# Kasli-SOC_power.net
KiCad netlist of a schematic drawn in Altium Designer
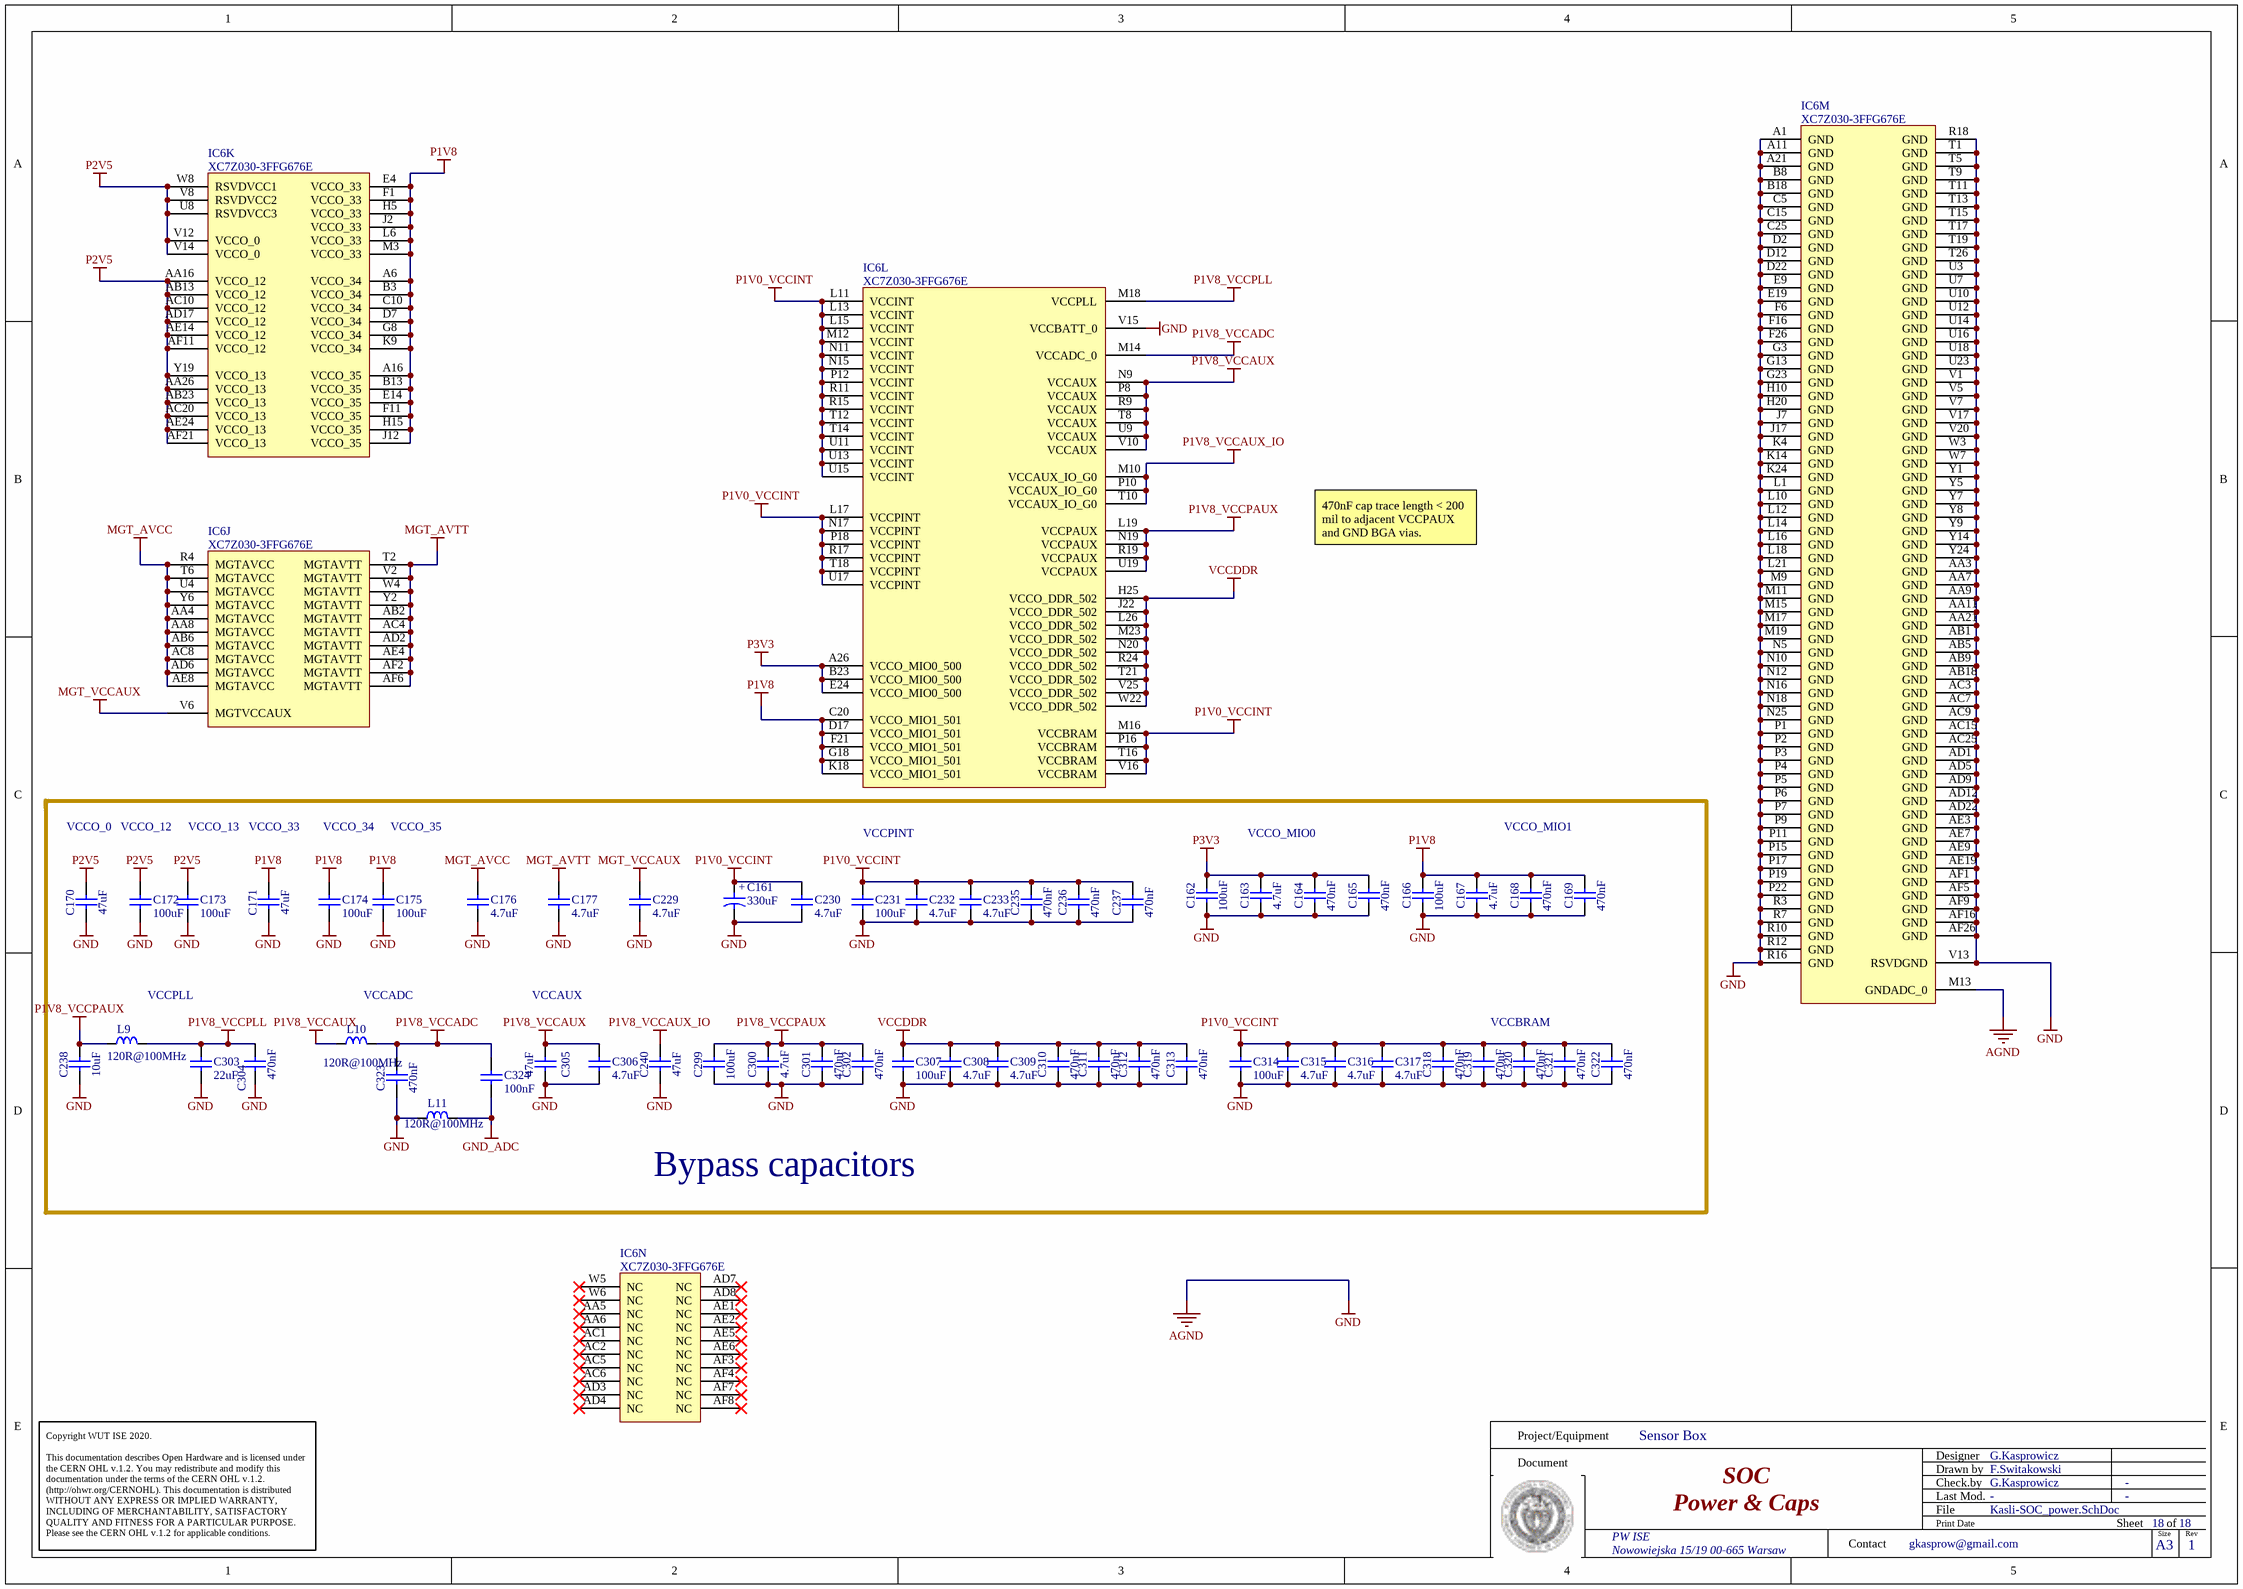
[diagram p0: Kasli-SOC_power.SchDoc]

(export (version "E")
  (design (tool "Eeschema 10.0.6"))
  (components
    (comp (ref "C161")
      (value "330uF")
      (footprint "CAPMP7343X310N")
      (description "Polarised capacitor")
      (fields
        (field (name "PART NUMBER") "CTE7343-31_330UF_6.3V_20%_LESR0015_KEMET_T520")
        (field (name "VOLTAGE") "6.3V")
        (field (name "AUTHOR") "CERN DEM JLC")
      )
      (libsource (lib "Capacitors") (part "Capacitor - polarized"))
    )
    (comp (ref "C162")
      (value "100uF")
      (footprint "CAPC3216X180N")
      (description "Non-polarised capacitor")
      (fields
        (field (name "PART NUMBER") "CC1206_100UF_6.3V_20%_X5R")
        (field (name "VOLTAGE") "6.3V")
        (field (name "AUTHOR") "CERN DEM JLC")
      )
      (libsource (lib "Capacitors") (part "Capacitor - non polarized"))
    )
    (comp (ref "C163")
      (value "4.7uF")
      (footprint "CAPC1005X55N")
      (description "Non-polarised capacitor")
      (fields
        (field (name "PART NUMBER") "CC0402_4.7UF_6.3V_20%_X5R")
        (field (name "VOLTAGE") "6.3V")
        (field (name "AUTHOR") "CERN DEM JLC")
      )
      (libsource (lib "Capacitors") (part "Capacitor - non polarized"))
    )
    (comp (ref "C164")
      (value "470nF")
      (footprint "CAPC1005X55N")
      (description "Non-polarised capacitor")
      (fields
        (field (name "PART NUMBER") "CC0402_470NF_16V_10%_X5R")
        (field (name "VOLTAGE") "16V")
        (field (name "AUTHOR") "CERN DEM JLC")
      )
      (libsource (lib "Capacitors") (part "Capacitor - non polarized"))
    )
    (comp (ref "C165")
      (value "470nF")
      (footprint "CAPC1005X55N")
      (description "Non-polarised capacitor")
      (fields
        (field (name "PART NUMBER") "CC0402_470NF_16V_10%_X5R")
        (field (name "VOLTAGE") "16V")
        (field (name "AUTHOR") "CERN DEM JLC")
      )
      (libsource (lib "Capacitors") (part "Capacitor - non polarized"))
    )
    (comp (ref "C166")
      (value "100uF")
      (footprint "CAPC3216X180N")
      (description "Non-polarised capacitor")
      (fields
        (field (name "PART NUMBER") "CC1206_100UF_6.3V_20%_X5R")
        (field (name "VOLTAGE") "6.3V")
        (field (name "AUTHOR") "CERN DEM JLC")
      )
      (libsource (lib "Capacitors") (part "Capacitor - non polarized"))
    )
    (comp (ref "C167")
      (value "4.7uF")
      (footprint "CAPC1005X55N")
      (description "Non-polarised capacitor")
      (fields
        (field (name "PART NUMBER") "CC0402_4.7UF_6.3V_20%_X5R")
        (field (name "VOLTAGE") "6.3V")
        (field (name "AUTHOR") "CERN DEM JLC")
      )
      (libsource (lib "Capacitors") (part "Capacitor - non polarized"))
    )
    (comp (ref "C168")
      (value "470nF")
      (footprint "CAPC1005X55N")
      (description "Non-polarised capacitor")
      (fields
        (field (name "PART NUMBER") "CC0402_470NF_16V_10%_X5R")
        (field (name "VOLTAGE") "16V")
        (field (name "AUTHOR") "CERN DEM JLC")
      )
      (libsource (lib "Capacitors") (part "Capacitor - non polarized"))
    )
    (comp (ref "C169")
      (value "470nF")
      (footprint "CAPC1005X55N")
      (description "Non-polarised capacitor")
      (fields
        (field (name "PART NUMBER") "CC0402_470NF_16V_10%_X5R")
        (field (name "VOLTAGE") "16V")
        (field (name "AUTHOR") "CERN DEM JLC")
      )
      (libsource (lib "Capacitors") (part "Capacitor - non polarized"))
    )
    (comp (ref "C170")
      (value "47uF")
      (footprint "CAPC3216X180N")
      (description "Non-polarised capacitor")
      (fields
        (field (name "PART NUMBER") "CC1206_47UF_10V_10%_X5R")
        (field (name "VOLTAGE") "10V")
        (field (name "AUTHOR") "CERN DEM MR")
      )
      (libsource (lib "Capacitors") (part "Capacitor - non polarized"))
    )
    (comp (ref "C171")
      (value "47uF")
      (footprint "CAPC3216X180N")
      (description "Non-polarised capacitor")
      (fields
        (field (name "PART NUMBER") "CC1206_47UF_10V_10%_X5R")
        (field (name "VOLTAGE") "10V")
        (field (name "AUTHOR") "CERN DEM MR")
      )
      (libsource (lib "Capacitors") (part "Capacitor - non polarized"))
    )
    (comp (ref "C172")
      (value "100uF")
      (footprint "CAPC3216X180N")
      (description "Non-polarised capacitor")
      (fields
        (field (name "PART NUMBER") "CC1206_100UF_6.3V_20%_X5R")
        (field (name "VOLTAGE") "6.3V")
        (field (name "AUTHOR") "CERN DEM JLC")
      )
      (libsource (lib "Capacitors") (part "Capacitor - non polarized"))
    )
    (comp (ref "C173")
      (value "100uF")
      (footprint "CAPC3216X180N")
      (description "Non-polarised capacitor")
      (fields
        (field (name "PART NUMBER") "CC1206_100UF_6.3V_20%_X5R")
        (field (name "VOLTAGE") "6.3V")
        (field (name "AUTHOR") "CERN DEM JLC")
      )
      (libsource (lib "Capacitors") (part "Capacitor - non polarized"))
    )
    (comp (ref "C174")
      (value "100uF")
      (footprint "CAPC3216X180N")
      (description "Non-polarised capacitor")
      (fields
        (field (name "PART NUMBER") "CC1206_100UF_6.3V_20%_X5R")
        (field (name "VOLTAGE") "6.3V")
        (field (name "AUTHOR") "CERN DEM JLC")
      )
      (libsource (lib "Capacitors") (part "Capacitor - non polarized"))
    )
    (comp (ref "C175")
      (value "100uF")
      (footprint "CAPC3216X180N")
      (description "Non-polarised capacitor")
      (fields
        (field (name "PART NUMBER") "CC1206_100UF_6.3V_20%_X5R")
        (field (name "VOLTAGE") "6.3V")
        (field (name "AUTHOR") "CERN DEM JLC")
      )
      (libsource (lib "Capacitors") (part "Capacitor - non polarized"))
    )
    (comp (ref "C176")
      (value "4.7uF")
      (footprint "CAPC1608X87N")
      (description "Non-polarised capacitor")
      (fields
        (field (name "PART NUMBER") "CC0603_4.7UF_6.3V_10%_X5R")
        (field (name "VOLTAGE") "6.3V")
        (field (name "AUTHOR") "CERN DEM JLC")
      )
      (libsource (lib "Capacitors") (part "Capacitor - non polarized"))
    )
    (comp (ref "C177")
      (value "4.7uF")
      (footprint "CAPC1608X87N")
      (description "Non-polarised capacitor")
      (fields
        (field (name "PART NUMBER") "CC0603_4.7UF_6.3V_10%_X5R")
        (field (name "VOLTAGE") "6.3V")
        (field (name "AUTHOR") "CERN DEM JLC")
      )
      (libsource (lib "Capacitors") (part "Capacitor - non polarized"))
    )
    (comp (ref "C229")
      (value "4.7uF")
      (footprint "CAPC1608X87N")
      (description "Non-polarised capacitor")
      (fields
        (field (name "PART NUMBER") "CC0603_4.7UF_6.3V_10%_X5R")
        (field (name "VOLTAGE") "6.3V")
        (field (name "AUTHOR") "CERN DEM JLC")
      )
      (libsource (lib "Capacitors") (part "Capacitor - non polarized"))
    )
    (comp (ref "C230")
      (value "4.7uF")
      (footprint "CAPC1608X87N")
      (description "Non-polarised capacitor")
      (fields
        (field (name "PART NUMBER") "CC0603_4.7UF_6.3V_10%_X5R")
        (field (name "VOLTAGE") "6.3V")
        (field (name "AUTHOR") "CERN DEM JLC")
      )
      (libsource (lib "Capacitors") (part "Capacitor - non polarized"))
    )
    (comp (ref "C231")
      (value "100uF")
      (footprint "CAPC3216X180N")
      (description "Non-polarised capacitor")
      (fields
        (field (name "PART NUMBER") "CC1206_100UF_6.3V_20%_X5R")
        (field (name "VOLTAGE") "6.3V")
        (field (name "AUTHOR") "CERN DEM JLC")
      )
      (libsource (lib "Capacitors") (part "Capacitor - non polarized"))
    )
    (comp (ref "C232")
      (value "4.7uF")
      (footprint "CAPC1608X87N")
      (description "Non-polarised capacitor")
      (fields
        (field (name "PART NUMBER") "CC0603_4.7UF_6.3V_10%_X5R")
        (field (name "VOLTAGE") "6.3V")
        (field (name "AUTHOR") "CERN DEM JLC")
      )
      (libsource (lib "Capacitors") (part "Capacitor - non polarized"))
    )
    (comp (ref "C233")
      (value "4.7uF")
      (footprint "CAPC1608X87N")
      (description "Non-polarised capacitor")
      (fields
        (field (name "PART NUMBER") "CC0603_4.7UF_6.3V_10%_X5R")
        (field (name "VOLTAGE") "6.3V")
        (field (name "AUTHOR") "CERN DEM JLC")
      )
      (libsource (lib "Capacitors") (part "Capacitor - non polarized"))
    )
    (comp (ref "C235")
      (value "470nF")
      (footprint "CAPC1005X55N")
      (description "Non-polarised capacitor")
      (fields
        (field (name "PART NUMBER") "CC0402_470NF_16V_10%_X5R")
        (field (name "VOLTAGE") "16V")
        (field (name "AUTHOR") "CERN DEM JLC")
      )
      (libsource (lib "Capacitors") (part "Capacitor - non polarized"))
    )
    (comp (ref "C236")
      (value "470nF")
      (footprint "CAPC1005X55N")
      (description "Non-polarised capacitor")
      (fields
        (field (name "PART NUMBER") "CC0402_470NF_16V_10%_X5R")
        (field (name "VOLTAGE") "16V")
        (field (name "AUTHOR") "CERN DEM JLC")
      )
      (libsource (lib "Capacitors") (part "Capacitor - non polarized"))
    )
    (comp (ref "C237")
      (value "470nF")
      (footprint "CAPC1005X55N")
      (description "Non-polarised capacitor")
      (fields
        (field (name "PART NUMBER") "CC0402_470NF_16V_10%_X5R")
        (field (name "VOLTAGE") "16V")
        (field (name "AUTHOR") "CERN DEM JLC")
      )
      (libsource (lib "Capacitors") (part "Capacitor - non polarized"))
    )
    (comp (ref "C238")
      (value "10uF")
      (footprint "CAPC1005X70N")
      (description "Non-polarised capacitor")
      (fields
        (field (name "PART NUMBER") "CC0402_10UF_6.3V_20%_X5R")
        (field (name "VOLTAGE") "6.3V")
        (field (name "AUTHOR") "CERN DEM JLC")
      )
      (libsource (lib "Capacitors") (part "Capacitor - non polarized"))
    )
    (comp (ref "C240")
      (value "47uF")
      (footprint "CAPC3216X180N")
      (description "Non-polarised capacitor")
      (fields
        (field (name "PART NUMBER") "CC1206_47UF_10V_10%_X5R")
        (field (name "VOLTAGE") "10V")
        (field (name "AUTHOR") "CERN DEM MR")
      )
      (libsource (lib "Capacitors") (part "Capacitor - non polarized"))
    )
    (comp (ref "C299")
      (value "100uF")
      (footprint "CAPC3216X180N")
      (description "Non-polarised capacitor")
      (fields
        (field (name "PART NUMBER") "CC1206_100UF_6.3V_20%_X5R")
        (field (name "VOLTAGE") "6.3V")
        (field (name "AUTHOR") "CERN DEM JLC")
      )
      (libsource (lib "Capacitors") (part "Capacitor - non polarized"))
    )
    (comp (ref "C300")
      (value "4.7uF")
      (footprint "CAPC1005X55N")
      (description "Non-polarised capacitor")
      (fields
        (field (name "PART NUMBER") "CC0402_4.7UF_6.3V_20%_X5R")
        (field (name "VOLTAGE") "6.3V")
        (field (name "AUTHOR") "CERN DEM JLC")
      )
      (libsource (lib "Capacitors") (part "Capacitor - non polarized"))
    )
    (comp (ref "C301")
      (value "470nF")
      (footprint "CAPC1005X55N")
      (description "Non-polarised capacitor")
      (fields
        (field (name "PART NUMBER") "CC0402_470NF_16V_10%_X5R")
        (field (name "VOLTAGE") "16V")
        (field (name "AUTHOR") "CERN DEM JLC")
      )
      (libsource (lib "Capacitors") (part "Capacitor - non polarized"))
    )
    (comp (ref "C302")
      (value "470nF")
      (footprint "CAPC1005X55N")
      (description "Non-polarised capacitor")
      (fields
        (field (name "PART NUMBER") "CC0402_470NF_16V_10%_X5R")
        (field (name "VOLTAGE") "16V")
        (field (name "AUTHOR") "CERN DEM JLC")
      )
      (libsource (lib "Capacitors") (part "Capacitor - non polarized"))
    )
    (comp (ref "C303")
      (value "22uF")
      (footprint "CAPC3216X180N")
      (description "Non-polarised capacitor")
      (fields
        (field (name "PART NUMBER") "CC1206_22UF_10V_10%_X7R")
        (field (name "VOLTAGE") "10V")
        (field (name "AUTHOR") "CERN DEM JLC")
      )
      (libsource (lib "Capacitors") (part "Capacitor - non polarized"))
    )
    (comp (ref "C304")
      (value "470nF")
      (footprint "CAPC1005X55N")
      (description "Non-polarised capacitor")
      (fields
        (field (name "PART NUMBER") "CC0402_470NF_16V_10%_X5R")
        (field (name "VOLTAGE") "16V")
        (field (name "AUTHOR") "CERN DEM JLC")
      )
      (libsource (lib "Capacitors") (part "Capacitor - non polarized"))
    )
    (comp (ref "C305")
      (value "47uF")
      (footprint "CAPC3216X180N")
      (description "Non-polarised capacitor")
      (fields
        (field (name "PART NUMBER") "CC1206_47UF_10V_10%_X5R")
        (field (name "VOLTAGE") "10V")
        (field (name "AUTHOR") "CERN DEM MR")
      )
      (libsource (lib "Capacitors") (part "Capacitor - non polarized"))
    )
    (comp (ref "C306")
      (value "4.7uF")
      (footprint "CAPC1608X87N")
      (description "Non-polarised capacitor")
      (fields
        (field (name "PART NUMBER") "CC0603_4.7UF_6.3V_10%_X5R")
        (field (name "VOLTAGE") "6.3V")
        (field (name "AUTHOR") "CERN DEM JLC")
      )
      (libsource (lib "Capacitors") (part "Capacitor - non polarized"))
    )
    (comp (ref "C307")
      (value "100uF")
      (footprint "CAPC3216X180N")
      (description "Non-polarised capacitor")
      (fields
        (field (name "PART NUMBER") "CC1206_100UF_6.3V_20%_X5R")
        (field (name "VOLTAGE") "6.3V")
        (field (name "AUTHOR") "CERN DEM JLC")
      )
      (libsource (lib "Capacitors") (part "Capacitor - non polarized"))
    )
    (comp (ref "C308")
      (value "4.7uF")
      (footprint "CAPC1608X87N")
      (description "Non-polarised capacitor")
      (fields
        (field (name "PART NUMBER") "CC0603_4.7UF_6.3V_10%_X5R")
        (field (name "VOLTAGE") "6.3V")
        (field (name "AUTHOR") "CERN DEM JLC")
      )
      (libsource (lib "Capacitors") (part "Capacitor - non polarized"))
    )
    (comp (ref "C309")
      (value "4.7uF")
      (footprint "CAPC1608X87N")
      (description "Non-polarised capacitor")
      (fields
        (field (name "PART NUMBER") "CC0603_4.7UF_6.3V_10%_X5R")
        (field (name "VOLTAGE") "6.3V")
        (field (name "AUTHOR") "CERN DEM JLC")
      )
      (libsource (lib "Capacitors") (part "Capacitor - non polarized"))
    )
    (comp (ref "C310")
      (value "470nF")
      (footprint "CAPC1005X55N")
      (description "Non-polarised capacitor")
      (fields
        (field (name "PART NUMBER") "CC0402_470NF_16V_10%_X5R")
        (field (name "VOLTAGE") "16V")
        (field (name "AUTHOR") "CERN DEM JLC")
      )
      (libsource (lib "Capacitors") (part "Capacitor - non polarized"))
    )
    (comp (ref "C311")
      (value "470nF")
      (footprint "CAPC1005X55N")
      (description "Non-polarised capacitor")
      (fields
        (field (name "PART NUMBER") "CC0402_470NF_16V_10%_X5R")
        (field (name "VOLTAGE") "16V")
        (field (name "AUTHOR") "CERN DEM JLC")
      )
      (libsource (lib "Capacitors") (part "Capacitor - non polarized"))
    )
    (comp (ref "C312")
      (value "470nF")
      (footprint "CAPC1005X55N")
      (description "Non-polarised capacitor")
      (fields
        (field (name "PART NUMBER") "CC0402_470NF_16V_10%_X5R")
        (field (name "VOLTAGE") "16V")
        (field (name "AUTHOR") "CERN DEM JLC")
      )
      (libsource (lib "Capacitors") (part "Capacitor - non polarized"))
    )
    (comp (ref "C313")
      (value "470nF")
      (footprint "CAPC1005X55N")
      (description "Non-polarised capacitor")
      (fields
        (field (name "PART NUMBER") "CC0402_470NF_16V_10%_X5R")
        (field (name "VOLTAGE") "16V")
        (field (name "AUTHOR") "CERN DEM JLC")
      )
      (libsource (lib "Capacitors") (part "Capacitor - non polarized"))
    )
    (comp (ref "C314")
      (value "100uF")
      (footprint "CAPC3216X180N")
      (description "Non-polarised capacitor")
      (fields
        (field (name "PART NUMBER") "CC1206_100UF_6.3V_20%_X5R")
        (field (name "VOLTAGE") "6.3V")
        (field (name "AUTHOR") "CERN DEM JLC")
      )
      (libsource (lib "Capacitors") (part "Capacitor - non polarized"))
    )
    (comp (ref "C315")
      (value "4.7uF")
      (footprint "CAPC1608X87N")
      (description "Non-polarised capacitor")
      (fields
        (field (name "PART NUMBER") "CC0603_4.7UF_6.3V_10%_X5R")
        (field (name "VOLTAGE") "6.3V")
        (field (name "AUTHOR") "CERN DEM JLC")
      )
      (libsource (lib "Capacitors") (part "Capacitor - non polarized"))
    )
    (comp (ref "C316")
      (value "4.7uF")
      (footprint "CAPC1608X87N")
      (description "Non-polarised capacitor")
      (fields
        (field (name "PART NUMBER") "CC0603_4.7UF_6.3V_10%_X5R")
        (field (name "VOLTAGE") "6.3V")
        (field (name "AUTHOR") "CERN DEM JLC")
      )
      (libsource (lib "Capacitors") (part "Capacitor - non polarized"))
    )
    (comp (ref "C317")
      (value "4.7uF")
      (footprint "CAPC1608X87N")
      (description "Non-polarised capacitor")
      (fields
        (field (name "PART NUMBER") "CC0603_4.7UF_6.3V_10%_X5R")
        (field (name "VOLTAGE") "6.3V")
        (field (name "AUTHOR") "CERN DEM JLC")
      )
      (libsource (lib "Capacitors") (part "Capacitor - non polarized"))
    )
    (comp (ref "C318")
      (value "470nF")
      (footprint "CAPC1005X55N")
      (description "Non-polarised capacitor")
      (fields
        (field (name "PART NUMBER") "CC0402_470NF_16V_10%_X5R")
        (field (name "VOLTAGE") "16V")
        (field (name "AUTHOR") "CERN DEM JLC")
      )
      (libsource (lib "Capacitors") (part "Capacitor - non polarized"))
    )
    (comp (ref "C319")
      (value "470nF")
      (footprint "CAPC1005X55N")
      (description "Non-polarised capacitor")
      (fields
        (field (name "PART NUMBER") "CC0402_470NF_16V_10%_X5R")
        (field (name "VOLTAGE") "16V")
        (field (name "AUTHOR") "CERN DEM JLC")
      )
      (libsource (lib "Capacitors") (part "Capacitor - non polarized"))
    )
    (comp (ref "C320")
      (value "470nF")
      (footprint "CAPC1005X55N")
      (description "Non-polarised capacitor")
      (fields
        (field (name "PART NUMBER") "CC0402_470NF_16V_10%_X5R")
        (field (name "VOLTAGE") "16V")
        (field (name "AUTHOR") "CERN DEM JLC")
      )
      (libsource (lib "Capacitors") (part "Capacitor - non polarized"))
    )
    (comp (ref "C321")
      (value "470nF")
      (footprint "CAPC1005X55N")
      (description "Non-polarised capacitor")
      (fields
        (field (name "PART NUMBER") "CC0402_470NF_16V_10%_X5R")
        (field (name "VOLTAGE") "16V")
        (field (name "AUTHOR") "CERN DEM JLC")
      )
      (libsource (lib "Capacitors") (part "Capacitor - non polarized"))
    )
    (comp (ref "C322")
      (value "470nF")
      (footprint "CAPC1005X55N")
      (description "Non-polarised capacitor")
      (fields
        (field (name "PART NUMBER") "CC0402_470NF_16V_10%_X5R")
        (field (name "VOLTAGE") "16V")
        (field (name "AUTHOR") "CERN DEM JLC")
      )
      (libsource (lib "Capacitors") (part "Capacitor - non polarized"))
    )
    (comp (ref "C323")
      (value "470nF")
      (footprint "CAPC1005X55N")
      (description "Non-polarised capacitor")
      (fields
        (field (name "PART NUMBER") "CC0402_470NF_16V_10%_X5R")
        (field (name "VOLTAGE") "16V")
        (field (name "AUTHOR") "CERN DEM JLC")
      )
      (libsource (lib "Capacitors") (part "Capacitor - non polarized"))
    )
    (comp (ref "C324")
      (value "100nF")
      (footprint "CAPC1005X55N")
      (description "Non-polarised capacitor")
      (fields
        (field (name "PART NUMBER") "CC0402_100NF_16V_10%_X7R")
        (field (name "VOLTAGE") "16V")
        (field (name "AUTHOR") "CERN DEM JLC")
      )
      (libsource (lib "Capacitors") (part "Capacitor - non polarized"))
    )
    (comp (ref "IC6")
      (value "XC7Z030-3FFG676E")
      (footprint "BGA676C100P26X26_2700X2700X324")
      (fields (field (name "MANUFACTURER") "XILINX") (field (name "AUTHOR") "CERN DEM JLC"))
      (libsource (lib "ICs And Semiconductors") (part "XC7Z030-2FFG676I"))
    )
    (comp (ref "L9")
      (value "120R@100MHz")
      (footprint "INDC1005X55N")
      (description "Inductor")
      (fields
        (field (name "PART NUMBER") "IND0402_MURATA_BLM15PX121SN1D")
        (field (name "POWER") "2A")
        (field (name "AUTHOR") "CERN DEM JMW")
      )
      (libsource (lib "Inductors & Transformers") (part "Inductor"))
    )
    (comp (ref "L10")
      (value "120R@100MHz")
      (footprint "INDC1005X55N")
      (description "Inductor")
      (fields
        (field (name "PART NUMBER") "IND0402_MURATA_BLM15PX121SN1D")
        (field (name "POWER") "2A")
        (field (name "AUTHOR") "CERN DEM JMW")
      )
      (libsource (lib "Inductors & Transformers") (part "Inductor"))
    )
    (comp (ref "L11")
      (value "120R@100MHz")
      (footprint "INDC1005X55N")
      (description "Inductor")
      (fields
        (field (name "PART NUMBER") "IND0402_MURATA_BLM15PX121SN1D")
        (field (name "POWER") "2A")
        (field (name "AUTHOR") "CERN DEM JMW")
      )
      (libsource (lib "Inductors & Transformers") (part "Inductor"))
    )
  )
  (nets
    (net (code "1") (name "AGND") (class "Default")
      (node (ref "C161") (pin "2") (pinfunction "2_2") (pintype "passive"))
      (node (ref "C162") (pin "1") (pinfunction "1_1") (pintype "passive"))
      (node (ref "C163") (pin "1") (pinfunction "1_1") (pintype "passive"))
      (node (ref "C164") (pin "1") (pinfunction "1_1") (pintype "passive"))
      (node (ref "C165") (pin "1") (pinfunction "1_1") (pintype "passive"))
      (node (ref "C166") (pin "1") (pinfunction "1_1") (pintype "passive"))
      (node (ref "C167") (pin "1") (pinfunction "1_1") (pintype "passive"))
      (node (ref "C168") (pin "1") (pinfunction "1_1") (pintype "passive"))
      (node (ref "C169") (pin "1") (pinfunction "1_1") (pintype "passive"))
      (node (ref "C170") (pin "1") (pinfunction "1_1") (pintype "passive"))
      (node (ref "C171") (pin "1") (pinfunction "1_1") (pintype "passive"))
      (node (ref "C172") (pin "2") (pinfunction "2_2") (pintype "passive"))
      (node (ref "C173") (pin "2") (pinfunction "2_2") (pintype "passive"))
      (node (ref "C174") (pin "2") (pinfunction "2_2") (pintype "passive"))
      (node (ref "C175") (pin "2") (pinfunction "2_2") (pintype "passive"))
      (node (ref "C176") (pin "1") (pinfunction "1_1") (pintype "passive"))
      (node (ref "C177") (pin "1") (pinfunction "1_1") (pintype "passive"))
      (node (ref "C229") (pin "1") (pinfunction "1_1") (pintype "passive"))
      (node (ref "C230") (pin "1") (pinfunction "1_1") (pintype "passive"))
      (node (ref "C231") (pin "2") (pinfunction "2_2") (pintype "passive"))
      (node (ref "C232") (pin "1") (pinfunction "1_1") (pintype "passive"))
      (node (ref "C233") (pin "1") (pinfunction "1_1") (pintype "passive"))
      (node (ref "C235") (pin "1") (pinfunction "1_1") (pintype "passive"))
      (node (ref "C236") (pin "1") (pinfunction "1_1") (pintype "passive"))
      (node (ref "C237") (pin "1") (pinfunction "1_1") (pintype "passive"))
      (node (ref "C238") (pin "1") (pinfunction "1_1") (pintype "passive"))
      (node (ref "C240") (pin "1") (pinfunction "1_1") (pintype "passive"))
      (node (ref "C299") (pin "1") (pinfunction "1_1") (pintype "passive"))
      (node (ref "C300") (pin "1") (pinfunction "1_1") (pintype "passive"))
      (node (ref "C301") (pin "1") (pinfunction "1_1") (pintype "passive"))
      (node (ref "C302") (pin "1") (pinfunction "1_1") (pintype "passive"))
      (node (ref "C303") (pin "2") (pinfunction "2_2") (pintype "passive"))
      (node (ref "C304") (pin "1") (pinfunction "1_1") (pintype "passive"))
      (node (ref "C305") (pin "2") (pinfunction "2_2") (pintype "passive"))
      (node (ref "C306") (pin "1") (pinfunction "1_1") (pintype "passive"))
      (node (ref "C307") (pin "2") (pinfunction "2_2") (pintype "passive"))
      (node (ref "C308") (pin "1") (pinfunction "1_1") (pintype "passive"))
      (node (ref "C309") (pin "1") (pinfunction "1_1") (pintype "passive"))
      (node (ref "C310") (pin "1") (pinfunction "1_1") (pintype "passive"))
      (node (ref "C311") (pin "1") (pinfunction "1_1") (pintype "passive"))
      (node (ref "C312") (pin "1") (pinfunction "1_1") (pintype "passive"))
      (node (ref "C313") (pin "1") (pinfunction "1_1") (pintype "passive"))
      (node (ref "C314") (pin "2") (pinfunction "2_2") (pintype "passive"))
      (node (ref "C315") (pin "1") (pinfunction "1_1") (pintype "passive"))
      (node (ref "C316") (pin "1") (pinfunction "1_1") (pintype "passive"))
      (node (ref "C317") (pin "1") (pinfunction "1_1") (pintype "passive"))
      (node (ref "C318") (pin "1") (pinfunction "1_1") (pintype "passive"))
      (node (ref "C319") (pin "1") (pinfunction "1_1") (pintype "passive"))
      (node (ref "C320") (pin "1") (pinfunction "1_1") (pintype "passive"))
      (node (ref "C321") (pin "1") (pinfunction "1_1") (pintype "passive"))
      (node (ref "C322") (pin "1") (pinfunction "1_1") (pintype "passive"))
      (node (ref "C323") (pin "1") (pinfunction "1_1") (pintype "passive"))
      (node (ref "IC6") (pin "A1") (pinfunction "GND_A1") (pintype "power_in"))
      (node (ref "IC6") (pin "A11") (pinfunction "GND_A11") (pintype "power_in"))
      (node (ref "IC6") (pin "A21") (pinfunction "GND_A21") (pintype "power_in"))
      (node (ref "IC6") (pin "AA11") (pinfunction "GND_AA11") (pintype "power_in"))
      (node (ref "IC6") (pin "AA21") (pinfunction "GND_AA21") (pintype "power_in"))
      (node (ref "IC6") (pin "AA3") (pinfunction "GND_AA3") (pintype "power_in"))
      (node (ref "IC6") (pin "AA7") (pinfunction "GND_AA7") (pintype "power_in"))
      (node (ref "IC6") (pin "AA9") (pinfunction "GND_AA9") (pintype "power_in"))
      (node (ref "IC6") (pin "AB1") (pinfunction "GND_AB1") (pintype "power_in"))
      (node (ref "IC6") (pin "AB18") (pinfunction "GND_AB18") (pintype "power_in"))
      (node (ref "IC6") (pin "AB5") (pinfunction "GND_AB5") (pintype "power_in"))
      (node (ref "IC6") (pin "AB9") (pinfunction "GND_AB9") (pintype "power_in"))
      (node (ref "IC6") (pin "AC15") (pinfunction "GND_AC15") (pintype "power_in"))
      (node (ref "IC6") (pin "AC25") (pinfunction "GND_AC25") (pintype "power_in"))
      (node (ref "IC6") (pin "AC3") (pinfunction "GND_AC3") (pintype "power_in"))
      (node (ref "IC6") (pin "AC7") (pinfunction "GND_AC7") (pintype "power_in"))
      (node (ref "IC6") (pin "AC9") (pinfunction "GND_AC9") (pintype "power_in"))
      (node (ref "IC6") (pin "AD1") (pinfunction "GND_AD1") (pintype "power_in"))
      (node (ref "IC6") (pin "AD12") (pinfunction "GND_AD12") (pintype "power_in"))
      (node (ref "IC6") (pin "AD22") (pinfunction "GND_AD22") (pintype "power_in"))
      (node (ref "IC6") (pin "AD5") (pinfunction "GND_AD5") (pintype "power_in"))
      (node (ref "IC6") (pin "AD9") (pinfunction "GND_AD9") (pintype "power_in"))
      (node (ref "IC6") (pin "AE19") (pinfunction "GND_AE19") (pintype "power_in"))
      (node (ref "IC6") (pin "AE3") (pinfunction "GND_AE3") (pintype "power_in"))
      (node (ref "IC6") (pin "AE7") (pinfunction "GND_AE7") (pintype "power_in"))
      (node (ref "IC6") (pin "AE9") (pinfunction "GND_AE9") (pintype "power_in"))
      (node (ref "IC6") (pin "AF1") (pinfunction "GND_AF1") (pintype "power_in"))
      (node (ref "IC6") (pin "AF16") (pinfunction "GND_AF16") (pintype "power_in"))
      (node (ref "IC6") (pin "AF26") (pinfunction "GND_AF26") (pintype "power_in"))
      (node (ref "IC6") (pin "AF5") (pinfunction "GND_AF5") (pintype "power_in"))
      (node (ref "IC6") (pin "AF9") (pinfunction "GND_AF9") (pintype "power_in"))
      (node (ref "IC6") (pin "B18") (pinfunction "GND_B18") (pintype "power_in"))
      (node (ref "IC6") (pin "B8") (pinfunction "GND_B8") (pintype "power_in"))
      (node (ref "IC6") (pin "C15") (pinfunction "GND_C15") (pintype "power_in"))
      (node (ref "IC6") (pin "C25") (pinfunction "GND_C25") (pintype "power_in"))
      (node (ref "IC6") (pin "C5") (pinfunction "GND_C5") (pintype "power_in"))
      (node (ref "IC6") (pin "D12") (pinfunction "GND_D12") (pintype "power_in"))
      (node (ref "IC6") (pin "D2") (pinfunction "GND_D2") (pintype "power_in"))
      (node (ref "IC6") (pin "D22") (pinfunction "GND_D22") (pintype "power_in"))
      (node (ref "IC6") (pin "E19") (pinfunction "GND_E19") (pintype "power_in"))
      (node (ref "IC6") (pin "E9") (pinfunction "GND_E9") (pintype "power_in"))
      (node (ref "IC6") (pin "F16") (pinfunction "GND_F16") (pintype "power_in"))
      (node (ref "IC6") (pin "F26") (pinfunction "GND_F26") (pintype "power_in"))
      (node (ref "IC6") (pin "F6") (pinfunction "GND_F6") (pintype "power_in"))
      (node (ref "IC6") (pin "G13") (pinfunction "GND_G13") (pintype "power_in"))
      (node (ref "IC6") (pin "G23") (pinfunction "GND_G23") (pintype "power_in"))
      (node (ref "IC6") (pin "G3") (pinfunction "GND_G3") (pintype "power_in"))
      (node (ref "IC6") (pin "H10") (pinfunction "GND_H10") (pintype "power_in"))
      (node (ref "IC6") (pin "H20") (pinfunction "GND_H20") (pintype "power_in"))
      (node (ref "IC6") (pin "J17") (pinfunction "GND_J17") (pintype "power_in"))
      (node (ref "IC6") (pin "J7") (pinfunction "GND_J7") (pintype "power_in"))
      (node (ref "IC6") (pin "K14") (pinfunction "GND_K14") (pintype "power_in"))
      (node (ref "IC6") (pin "K24") (pinfunction "GND_K24") (pintype "power_in"))
      (node (ref "IC6") (pin "K4") (pinfunction "GND_K4") (pintype "power_in"))
      (node (ref "IC6") (pin "L1") (pinfunction "GND_L1") (pintype "power_in"))
      (node (ref "IC6") (pin "L10") (pinfunction "GND_L10") (pintype "power_in"))
      (node (ref "IC6") (pin "L12") (pinfunction "GND_L12") (pintype "power_in"))
      (node (ref "IC6") (pin "L14") (pinfunction "GND_L14") (pintype "power_in"))
      (node (ref "IC6") (pin "L16") (pinfunction "GND_L16") (pintype "power_in"))
      (node (ref "IC6") (pin "L18") (pinfunction "GND_L18") (pintype "power_in"))
      (node (ref "IC6") (pin "L21") (pinfunction "GND_L21") (pintype "power_in"))
      (node (ref "IC6") (pin "M11") (pinfunction "GND_M11") (pintype "power_in"))
      (node (ref "IC6") (pin "M13") (pinfunction "GNDADC_0_M13") (pintype "power_in"))
      (node (ref "IC6") (pin "M15") (pinfunction "GND_M15") (pintype "power_in"))
      (node (ref "IC6") (pin "M17") (pinfunction "GND_M17") (pintype "power_in"))
      (node (ref "IC6") (pin "M19") (pinfunction "GND_M19") (pintype "power_in"))
      (node (ref "IC6") (pin "M9") (pinfunction "GND_M9") (pintype "power_in"))
      (node (ref "IC6") (pin "N10") (pinfunction "GND_N10") (pintype "power_in"))
      (node (ref "IC6") (pin "N12") (pinfunction "GND_N12") (pintype "power_in"))
      (node (ref "IC6") (pin "N16") (pinfunction "GND_N16") (pintype "power_in"))
      (node (ref "IC6") (pin "N18") (pinfunction "GND_N18") (pintype "power_in"))
      (node (ref "IC6") (pin "N25") (pinfunction "GND_N25") (pintype "power_in"))
      (node (ref "IC6") (pin "N5") (pinfunction "GND_N5") (pintype "power_in"))
      (node (ref "IC6") (pin "P1") (pinfunction "GND_P1") (pintype "power_in"))
      (node (ref "IC6") (pin "P11") (pinfunction "GND_P11") (pintype "power_in"))
      (node (ref "IC6") (pin "P15") (pinfunction "GND_P15") (pintype "power_in"))
      (node (ref "IC6") (pin "P17") (pinfunction "GND_P17") (pintype "power_in"))
      (node (ref "IC6") (pin "P19") (pinfunction "GND_P19") (pintype "power_in"))
      (node (ref "IC6") (pin "P2") (pinfunction "GND_P2") (pintype "power_in"))
      (node (ref "IC6") (pin "P22") (pinfunction "GND_P22") (pintype "power_in"))
      (node (ref "IC6") (pin "P3") (pinfunction "GND_P3") (pintype "power_in"))
      (node (ref "IC6") (pin "P4") (pinfunction "GND_P4") (pintype "power_in"))
      (node (ref "IC6") (pin "P5") (pinfunction "GND_P5") (pintype "power_in"))
      (node (ref "IC6") (pin "P6") (pinfunction "GND_P6") (pintype "power_in"))
      (node (ref "IC6") (pin "P7") (pinfunction "GND_P7") (pintype "power_in"))
      (node (ref "IC6") (pin "P9") (pinfunction "GND_P9") (pintype "power_in"))
      (node (ref "IC6") (pin "R10") (pinfunction "GND_R10") (pintype "power_in"))
      (node (ref "IC6") (pin "R12") (pinfunction "GND_R12") (pintype "power_in"))
      (node (ref "IC6") (pin "R16") (pinfunction "GND_R16") (pintype "power_in"))
      (node (ref "IC6") (pin "R18") (pinfunction "GND_R18") (pintype "power_in"))
      (node (ref "IC6") (pin "R3") (pinfunction "GND_R3") (pintype "power_in"))
      (node (ref "IC6") (pin "R7") (pinfunction "GND_R7") (pintype "power_in"))
      (node (ref "IC6") (pin "T1") (pinfunction "GND_T1") (pintype "power_in"))
      (node (ref "IC6") (pin "T11") (pinfunction "GND_T11") (pintype "power_in"))
      (node (ref "IC6") (pin "T13") (pinfunction "GND_T13") (pintype "power_in"))
      (node (ref "IC6") (pin "T15") (pinfunction "GND_T15") (pintype "power_in"))
      (node (ref "IC6") (pin "T17") (pinfunction "GND_T17") (pintype "power_in"))
      (node (ref "IC6") (pin "T19") (pinfunction "GND_T19") (pintype "power_in"))
      (node (ref "IC6") (pin "T26") (pinfunction "GND_T26") (pintype "power_in"))
      (node (ref "IC6") (pin "T5") (pinfunction "GND_T5") (pintype "power_in"))
      (node (ref "IC6") (pin "T9") (pinfunction "GND_T9") (pintype "power_in"))
      (node (ref "IC6") (pin "U10") (pinfunction "GND_U10") (pintype "power_in"))
      (node (ref "IC6") (pin "U12") (pinfunction "GND_U12") (pintype "power_in"))
      (node (ref "IC6") (pin "U14") (pinfunction "GND_U14") (pintype "power_in"))
      (node (ref "IC6") (pin "U16") (pinfunction "GND_U16") (pintype "power_in"))
      (node (ref "IC6") (pin "U18") (pinfunction "GND_U18") (pintype "power_in"))
      (node (ref "IC6") (pin "U23") (pinfunction "GND_U23") (pintype "power_in"))
      (node (ref "IC6") (pin "U3") (pinfunction "GND_U3") (pintype "power_in"))
      (node (ref "IC6") (pin "U7") (pinfunction "GND_U7") (pintype "power_in"))
      (node (ref "IC6") (pin "V1") (pinfunction "GND_V1") (pintype "power_in"))
      (node (ref "IC6") (pin "V13") (pinfunction "RSVDGND_V13") (pintype "power_in"))
      (node (ref "IC6") (pin "V15") (pinfunction "VCCBATT_0_V15") (pintype "power_in"))
      (node (ref "IC6") (pin "V17") (pinfunction "GND_V17") (pintype "power_in"))
      (node (ref "IC6") (pin "V20") (pinfunction "GND_V20") (pintype "power_in"))
      (node (ref "IC6") (pin "V5") (pinfunction "GND_V5") (pintype "power_in"))
      (node (ref "IC6") (pin "V7") (pinfunction "GND_V7") (pintype "power_in"))
      (node (ref "IC6") (pin "W3") (pinfunction "GND_W3") (pintype "power_in"))
      (node (ref "IC6") (pin "W7") (pinfunction "GND_W7") (pintype "power_in"))
      (node (ref "IC6") (pin "Y1") (pinfunction "GND_Y1") (pintype "power_in"))
      (node (ref "IC6") (pin "Y14") (pinfunction "GND_Y14") (pintype "power_in"))
      (node (ref "IC6") (pin "Y24") (pinfunction "GND_Y24") (pintype "power_in"))
      (node (ref "IC6") (pin "Y5") (pinfunction "GND_Y5") (pintype "power_in"))
      (node (ref "IC6") (pin "Y7") (pinfunction "GND_Y7") (pintype "power_in"))
      (node (ref "IC6") (pin "Y8") (pinfunction "GND_Y8") (pintype "power_in"))
      (node (ref "IC6") (pin "Y9") (pinfunction "GND_Y9") (pintype "power_in"))
      (node (ref "L11") (pin "1") (pinfunction "1_1") (pintype "passive"))
    )
    (net (code "2") (name "GND_ADC") (class "Default")
      (node (ref "C324") (pin "1") (pinfunction "1_1") (pintype "passive"))
      (node (ref "L11") (pin "2") (pinfunction "2_2") (pintype "passive"))
    )
    (net (code "3") (name "MGT_AVCC") (class "Default")
      (node (ref "C176") (pin "2") (pinfunction "2_2") (pintype "passive"))
      (node (ref "IC6") (pin "AA4") (pinfunction "MGTAVCC_AA4") (pintype "power_in"))
      (node (ref "IC6") (pin "AA8") (pinfunction "MGTAVCC_AA8") (pintype "power_in"))
      (node (ref "IC6") (pin "AB6") (pinfunction "MGTAVCC_AB6") (pintype "power_in"))
      (node (ref "IC6") (pin "AC8") (pinfunction "MGTAVCC_AC8") (pintype "power_in"))
      (node (ref "IC6") (pin "AD6") (pinfunction "MGTAVCC_AD6") (pintype "power_in"))
      (node (ref "IC6") (pin "AE8") (pinfunction "MGTAVCC_AE8") (pintype "power_in"))
      (node (ref "IC6") (pin "R4") (pinfunction "MGTAVCC_R4") (pintype "power_in"))
      (node (ref "IC6") (pin "T6") (pinfunction "MGTAVCC_T6") (pintype "power_in"))
      (node (ref "IC6") (pin "U4") (pinfunction "MGTAVCC_U4") (pintype "power_in"))
      (node (ref "IC6") (pin "Y6") (pinfunction "MGTAVCC_Y6") (pintype "power_in"))
    )
    (net (code "4") (name "MGT_AVTT") (class "Default")
      (node (ref "C177") (pin "2") (pinfunction "2_2") (pintype "passive"))
      (node (ref "IC6") (pin "AB2") (pinfunction "MGTAVTT_AB2") (pintype "power_in"))
      (node (ref "IC6") (pin "AC4") (pinfunction "MGTAVTT_AC4") (pintype "power_in"))
      (node (ref "IC6") (pin "AD2") (pinfunction "MGTAVTT_AD2") (pintype "power_in"))
      (node (ref "IC6") (pin "AE4") (pinfunction "MGTAVTT_AE4") (pintype "power_in"))
      (node (ref "IC6") (pin "AF2") (pinfunction "MGTAVTT_AF2") (pintype "power_in"))
      (node (ref "IC6") (pin "AF6") (pinfunction "MGTAVTT_AF6") (pintype "power_in"))
      (node (ref "IC6") (pin "T2") (pinfunction "MGTAVTT_T2") (pintype "power_in"))
      (node (ref "IC6") (pin "V2") (pinfunction "MGTAVTT_V2") (pintype "power_in"))
      (node (ref "IC6") (pin "W4") (pinfunction "MGTAVTT_W4") (pintype "power_in"))
      (node (ref "IC6") (pin "Y2") (pinfunction "MGTAVTT_Y2") (pintype "power_in"))
    )
    (net (code "5") (name "MGT_VCCAUX") (class "Default")
      (node (ref "C229") (pin "2") (pinfunction "2_2") (pintype "passive"))
      (node (ref "IC6") (pin "V6") (pinfunction "MGTVCCAUX_V6") (pintype "power_in"))
    )
    (net (code "6") (name "P1V0_VCCINT") (class "Default")
      (node (ref "C161") (pin "1") (pinfunction "1_1") (pintype "passive"))
      (node (ref "C230") (pin "2") (pinfunction "2_2") (pintype "passive"))
      (node (ref "C231") (pin "1") (pinfunction "1_1") (pintype "passive"))
      (node (ref "C232") (pin "2") (pinfunction "2_2") (pintype "passive"))
      (node (ref "C233") (pin "2") (pinfunction "2_2") (pintype "passive"))
      (node (ref "C235") (pin "2") (pinfunction "2_2") (pintype "passive"))
      (node (ref "C236") (pin "2") (pinfunction "2_2") (pintype "passive"))
      (node (ref "C237") (pin "2") (pinfunction "2_2") (pintype "passive"))
      (node (ref "C314") (pin "1") (pinfunction "1_1") (pintype "passive"))
      (node (ref "C315") (pin "2") (pinfunction "2_2") (pintype "passive"))
      (node (ref "C316") (pin "2") (pinfunction "2_2") (pintype "passive"))
      (node (ref "C317") (pin "2") (pinfunction "2_2") (pintype "passive"))
      (node (ref "C318") (pin "2") (pinfunction "2_2") (pintype "passive"))
      (node (ref "C319") (pin "2") (pinfunction "2_2") (pintype "passive"))
      (node (ref "C320") (pin "2") (pinfunction "2_2") (pintype "passive"))
      (node (ref "C321") (pin "2") (pinfunction "2_2") (pintype "passive"))
      (node (ref "C322") (pin "2") (pinfunction "2_2") (pintype "passive"))
      (node (ref "IC6") (pin "L11") (pinfunction "VCCINT_L11") (pintype "power_in"))
      (node (ref "IC6") (pin "L13") (pinfunction "VCCINT_L13") (pintype "power_in"))
      (node (ref "IC6") (pin "L15") (pinfunction "VCCINT_L15") (pintype "power_in"))
      (node (ref "IC6") (pin "L17") (pinfunction "VCCPINT_L17") (pintype "power_in"))
      (node (ref "IC6") (pin "M12") (pinfunction "VCCINT_M12") (pintype "power_in"))
      (node (ref "IC6") (pin "M16") (pinfunction "VCCBRAM_M16") (pintype "power_in"))
      (node (ref "IC6") (pin "N11") (pinfunction "VCCINT_N11") (pintype "power_in"))
      (node (ref "IC6") (pin "N15") (pinfunction "VCCINT_N15") (pintype "power_in"))
      (node (ref "IC6") (pin "N17") (pinfunction "VCCPINT_N17") (pintype "power_in"))
      (node (ref "IC6") (pin "P12") (pinfunction "VCCINT_P12") (pintype "power_in"))
      (node (ref "IC6") (pin "P16") (pinfunction "VCCBRAM_P16") (pintype "power_in"))
      (node (ref "IC6") (pin "P18") (pinfunction "VCCPINT_P18") (pintype "power_in"))
      (node (ref "IC6") (pin "R11") (pinfunction "VCCINT_R11") (pintype "power_in"))
      (node (ref "IC6") (pin "R15") (pinfunction "VCCINT_R15") (pintype "power_in"))
      (node (ref "IC6") (pin "R17") (pinfunction "VCCPINT_R17") (pintype "power_in"))
      (node (ref "IC6") (pin "T12") (pinfunction "VCCINT_T12") (pintype "power_in"))
      (node (ref "IC6") (pin "T14") (pinfunction "VCCINT_T14") (pintype "power_in"))
      (node (ref "IC6") (pin "T16") (pinfunction "VCCBRAM_T16") (pintype "power_in"))
      (node (ref "IC6") (pin "T18") (pinfunction "VCCPINT_T18") (pintype "power_in"))
      (node (ref "IC6") (pin "U11") (pinfunction "VCCINT_U11") (pintype "power_in"))
      (node (ref "IC6") (pin "U13") (pinfunction "VCCINT_U13") (pintype "power_in"))
      (node (ref "IC6") (pin "U15") (pinfunction "VCCINT_U15") (pintype "power_in"))
      (node (ref "IC6") (pin "U17") (pinfunction "VCCPINT_U17") (pintype "power_in"))
      (node (ref "IC6") (pin "V16") (pinfunction "VCCBRAM_V16") (pintype "power_in"))
    )
    (net (code "7") (name "P1V8") (class "Default")
      (node (ref "C166") (pin "2") (pinfunction "2_2") (pintype "passive"))
      (node (ref "C167") (pin "2") (pinfunction "2_2") (pintype "passive"))
      (node (ref "C168") (pin "2") (pinfunction "2_2") (pintype "passive"))
      (node (ref "C169") (pin "2") (pinfunction "2_2") (pintype "passive"))
      (node (ref "C171") (pin "2") (pinfunction "2_2") (pintype "passive"))
      (node (ref "C174") (pin "1") (pinfunction "1_1") (pintype "passive"))
      (node (ref "C175") (pin "1") (pinfunction "1_1") (pintype "passive"))
      (node (ref "IC6") (pin "A16") (pinfunction "VCCO_35_A16") (pintype "power_in"))
      (node (ref "IC6") (pin "A6") (pinfunction "VCCO_34_A6") (pintype "power_in"))
      (node (ref "IC6") (pin "B13") (pinfunction "VCCO_35_B13") (pintype "power_in"))
      (node (ref "IC6") (pin "B3") (pinfunction "VCCO_34_B3") (pintype "power_in"))
      (node (ref "IC6") (pin "C10") (pinfunction "VCCO_34_C10") (pintype "power_in"))
      (node (ref "IC6") (pin "C20") (pinfunction "VCCO_MIO1_501_C20") (pintype "power_in"))
      (node (ref "IC6") (pin "D17") (pinfunction "VCCO_MIO1_501_D17") (pintype "power_in"))
      (node (ref "IC6") (pin "D7") (pinfunction "VCCO_34_D7") (pintype "power_in"))
      (node (ref "IC6") (pin "E14") (pinfunction "VCCO_35_E14") (pintype "power_in"))
      (node (ref "IC6") (pin "E4") (pinfunction "VCCO_33_E4") (pintype "power_in"))
      (node (ref "IC6") (pin "F1") (pinfunction "VCCO_33_F1") (pintype "power_in"))
      (node (ref "IC6") (pin "F11") (pinfunction "VCCO_35_F11") (pintype "power_in"))
      (node (ref "IC6") (pin "F21") (pinfunction "VCCO_MIO1_501_F21") (pintype "power_in"))
      (node (ref "IC6") (pin "G18") (pinfunction "VCCO_MIO1_501_G18") (pintype "power_in"))
      (node (ref "IC6") (pin "G8") (pinfunction "VCCO_34_G8") (pintype "power_in"))
      (node (ref "IC6") (pin "H15") (pinfunction "VCCO_35_H15") (pintype "power_in"))
      (node (ref "IC6") (pin "H5") (pinfunction "VCCO_33_H5") (pintype "power_in"))
      (node (ref "IC6") (pin "J12") (pinfunction "VCCO_35_J12") (pintype "power_in"))
      (node (ref "IC6") (pin "J2") (pinfunction "VCCO_33_J2") (pintype "power_in"))
      (node (ref "IC6") (pin "K18") (pinfunction "VCCO_MIO1_501_K18") (pintype "power_in"))
      (node (ref "IC6") (pin "K9") (pinfunction "VCCO_34_K9") (pintype "power_in"))
      (node (ref "IC6") (pin "L6") (pinfunction "VCCO_33_L6") (pintype "power_in"))
      (node (ref "IC6") (pin "M3") (pinfunction "VCCO_33_M3") (pintype "power_in"))
    )
    (net (code "8") (name "P1V8_VCCADC") (class "Default")
      (node (ref "C323") (pin "2") (pinfunction "2_2") (pintype "passive"))
      (node (ref "C324") (pin "2") (pinfunction "2_2") (pintype "passive"))
      (node (ref "IC6") (pin "M14") (pinfunction "VCCADC_0_M14") (pintype "power_in"))
      (node (ref "L10") (pin "2") (pinfunction "2_2") (pintype "passive"))
    )
    (net (code "9") (name "P1V8_VCCAUX") (class "Default")
      (node (ref "C305") (pin "1") (pinfunction "1_1") (pintype "passive"))
      (node (ref "C306") (pin "2") (pinfunction "2_2") (pintype "passive"))
      (node (ref "IC6") (pin "N9") (pinfunction "VCCAUX_N9") (pintype "power_in"))
      (node (ref "IC6") (pin "P8") (pinfunction "VCCAUX_P8") (pintype "power_in"))
      (node (ref "IC6") (pin "R9") (pinfunction "VCCAUX_R9") (pintype "power_in"))
      (node (ref "IC6") (pin "T8") (pinfunction "VCCAUX_T8") (pintype "power_in"))
      (node (ref "IC6") (pin "U9") (pinfunction "VCCAUX_U9") (pintype "power_in"))
      (node (ref "IC6") (pin "V10") (pinfunction "VCCAUX_V10") (pintype "power_in"))
      (node (ref "L10") (pin "1") (pinfunction "1_1") (pintype "passive"))
    )
    (net (code "10") (name "P1V8_VCCAUX_IO") (class "Default")
      (node (ref "C240") (pin "2") (pinfunction "2_2") (pintype "passive"))
      (node (ref "IC6") (pin "M10") (pinfunction "VCCAUX_IO_G0_M10") (pintype "power_in"))
      (node (ref "IC6") (pin "P10") (pinfunction "VCCAUX_IO_G0_P10") (pintype "power_in"))
      (node (ref "IC6") (pin "T10") (pinfunction "VCCAUX_IO_G0_T10") (pintype "power_in"))
    )
    (net (code "11") (name "P1V8_VCCPAUX") (class "Default")
      (node (ref "C238") (pin "2") (pinfunction "2_2") (pintype "passive"))
      (node (ref "C299") (pin "2") (pinfunction "2_2") (pintype "passive"))
      (node (ref "C300") (pin "2") (pinfunction "2_2") (pintype "passive"))
      (node (ref "C301") (pin "2") (pinfunction "2_2") (pintype "passive"))
      (node (ref "C302") (pin "2") (pinfunction "2_2") (pintype "passive"))
      (node (ref "IC6") (pin "L19") (pinfunction "VCCPAUX_L19") (pintype "power_in"))
      (node (ref "IC6") (pin "N19") (pinfunction "VCCPAUX_N19") (pintype "power_in"))
      (node (ref "IC6") (pin "R19") (pinfunction "VCCPAUX_R19") (pintype "power_in"))
      (node (ref "IC6") (pin "U19") (pinfunction "VCCPAUX_U19") (pintype "power_in"))
      (node (ref "L9") (pin "1") (pinfunction "1_1") (pintype "passive"))
    )
    (net (code "12") (name "P1V8_VCCPLL") (class "Default")
      (node (ref "C303") (pin "1") (pinfunction "1_1") (pintype "passive"))
      (node (ref "C304") (pin "2") (pinfunction "2_2") (pintype "passive"))
      (node (ref "IC6") (pin "M18") (pinfunction "VCCPLL_M18") (pintype "power_in"))
      (node (ref "L9") (pin "2") (pinfunction "2_2") (pintype "passive"))
    )
    (net (code "13") (name "P2V5") (class "Default")
      (node (ref "C170") (pin "2") (pinfunction "2_2") (pintype "passive"))
      (node (ref "C172") (pin "1") (pinfunction "1_1") (pintype "passive"))
      (node (ref "C173") (pin "1") (pinfunction "1_1") (pintype "passive"))
      (node (ref "IC6") (pin "AA16") (pinfunction "VCCO_12_AA16") (pintype "power_in"))
      (node (ref "IC6") (pin "AA26") (pinfunction "VCCO_13_AA26") (pintype "power_in"))
      (node (ref "IC6") (pin "AB13") (pinfunction "VCCO_12_AB13") (pintype "power_in"))
      (node (ref "IC6") (pin "AB23") (pinfunction "VCCO_13_AB23") (pintype "power_in"))
      (node (ref "IC6") (pin "AC10") (pinfunction "VCCO_12_AC10") (pintype "power_in"))
      (node (ref "IC6") (pin "AC20") (pinfunction "VCCO_13_AC20") (pintype "power_in"))
      (node (ref "IC6") (pin "AD17") (pinfunction "VCCO_12_AD17") (pintype "power_in"))
      (node (ref "IC6") (pin "AE14") (pinfunction "VCCO_12_AE14") (pintype "power_in"))
      (node (ref "IC6") (pin "AE24") (pinfunction "VCCO_13_AE24") (pintype "power_in"))
      (node (ref "IC6") (pin "AF11") (pinfunction "VCCO_12_AF11") (pintype "power_in"))
      (node (ref "IC6") (pin "AF21") (pinfunction "VCCO_13_AF21") (pintype "power_in"))
      (node (ref "IC6") (pin "U8") (pinfunction "RSVDVCC3_U8") (pintype "power_in"))
      (node (ref "IC6") (pin "V12") (pinfunction "VCCO_0_V12") (pintype "power_in"))
      (node (ref "IC6") (pin "V14") (pinfunction "VCCO_0_V14") (pintype "power_in"))
      (node (ref "IC6") (pin "V8") (pinfunction "RSVDVCC2_V8") (pintype "power_in"))
      (node (ref "IC6") (pin "W8") (pinfunction "RSVDVCC1_W8") (pintype "power_in"))
      (node (ref "IC6") (pin "Y19") (pinfunction "VCCO_13_Y19") (pintype "power_in"))
    )
    (net (code "14") (name "P3V3") (class "Default")
      (node (ref "C162") (pin "2") (pinfunction "2_2") (pintype "passive"))
      (node (ref "C163") (pin "2") (pinfunction "2_2") (pintype "passive"))
      (node (ref "C164") (pin "2") (pinfunction "2_2") (pintype "passive"))
      (node (ref "C165") (pin "2") (pinfunction "2_2") (pintype "passive"))
      (node (ref "IC6") (pin "A26") (pinfunction "VCCO_MIO0_500_A26") (pintype "power_in"))
      (node (ref "IC6") (pin "B23") (pinfunction "VCCO_MIO0_500_B23") (pintype "power_in"))
      (node (ref "IC6") (pin "E24") (pinfunction "VCCO_MIO0_500_E24") (pintype "power_in"))
    )
    (net (code "15") (name "VCCDDR") (class "Default")
      (node (ref "C307") (pin "1") (pinfunction "1_1") (pintype "passive"))
      (node (ref "C308") (pin "2") (pinfunction "2_2") (pintype "passive"))
      (node (ref "C309") (pin "2") (pinfunction "2_2") (pintype "passive"))
      (node (ref "C310") (pin "2") (pinfunction "2_2") (pintype "passive"))
      (node (ref "C311") (pin "2") (pinfunction "2_2") (pintype "passive"))
      (node (ref "C312") (pin "2") (pinfunction "2_2") (pintype "passive"))
      (node (ref "C313") (pin "2") (pinfunction "2_2") (pintype "passive"))
      (node (ref "IC6") (pin "H25") (pinfunction "VCCO_DDR_502_H25") (pintype "power_in"))
      (node (ref "IC6") (pin "J22") (pinfunction "VCCO_DDR_502_J22") (pintype "power_in"))
      (node (ref "IC6") (pin "L26") (pinfunction "VCCO_DDR_502_L26") (pintype "power_in"))
      (node (ref "IC6") (pin "M23") (pinfunction "VCCO_DDR_502_M23") (pintype "power_in"))
      (node (ref "IC6") (pin "N20") (pinfunction "VCCO_DDR_502_N20") (pintype "power_in"))
      (node (ref "IC6") (pin "R24") (pinfunction "VCCO_DDR_502_R24") (pintype "power_in"))
      (node (ref "IC6") (pin "T21") (pinfunction "VCCO_DDR_502_T21") (pintype "power_in"))
      (node (ref "IC6") (pin "V25") (pinfunction "VCCO_DDR_502_V25") (pintype "power_in"))
      (node (ref "IC6") (pin "W22") (pinfunction "VCCO_DDR_502_W22") (pintype "power_in"))
    )
    (net (code "16") (name "unconnected-(IC6N-NC-PadAA5)") (class "Default")
      (node (ref "IC6") (pin "AA5") (pinfunction "NC_AA5") (pintype "passive+no_connect"))
    )
    (net (code "17") (name "unconnected-(IC6N-NC-PadAA6)") (class "Default")
      (node (ref "IC6") (pin "AA6") (pinfunction "NC_AA6") (pintype "passive+no_connect"))
    )
    (net (code "18") (name "unconnected-(IC6N-NC-PadAC1)") (class "Default")
      (node (ref "IC6") (pin "AC1") (pinfunction "NC_AC1") (pintype "passive+no_connect"))
    )
    (net (code "19") (name "unconnected-(IC6N-NC-PadAC2)") (class "Default")
      (node (ref "IC6") (pin "AC2") (pinfunction "NC_AC2") (pintype "passive+no_connect"))
    )
    (net (code "20") (name "unconnected-(IC6N-NC-PadAC5)") (class "Default")
      (node (ref "IC6") (pin "AC5") (pinfunction "NC_AC5") (pintype "passive+no_connect"))
    )
    (net (code "21") (name "unconnected-(IC6N-NC-PadAC6)") (class "Default")
      (node (ref "IC6") (pin "AC6") (pinfunction "NC_AC6") (pintype "passive+no_connect"))
    )
    (net (code "22") (name "unconnected-(IC6N-NC-PadAD3)") (class "Default")
      (node (ref "IC6") (pin "AD3") (pinfunction "NC_AD3") (pintype "passive+no_connect"))
    )
    (net (code "23") (name "unconnected-(IC6N-NC-PadAD4)") (class "Default")
      (node (ref "IC6") (pin "AD4") (pinfunction "NC_AD4") (pintype "passive+no_connect"))
    )
    (net (code "24") (name "unconnected-(IC6N-NC-PadAD7)") (class "Default")
      (node (ref "IC6") (pin "AD7") (pinfunction "NC_AD7") (pintype "passive+no_connect"))
    )
    (net (code "25") (name "unconnected-(IC6N-NC-PadAD8)") (class "Default")
      (node (ref "IC6") (pin "AD8") (pinfunction "NC_AD8") (pintype "passive+no_connect"))
    )
    (net (code "26") (name "unconnected-(IC6N-NC-PadAE1)") (class "Default")
      (node (ref "IC6") (pin "AE1") (pinfunction "NC_AE1") (pintype "passive+no_connect"))
    )
    (net (code "27") (name "unconnected-(IC6N-NC-PadAE2)") (class "Default")
      (node (ref "IC6") (pin "AE2") (pinfunction "NC_AE2") (pintype "passive+no_connect"))
    )
    (net (code "28") (name "unconnected-(IC6N-NC-PadAE5)") (class "Default")
      (node (ref "IC6") (pin "AE5") (pinfunction "NC_AE5") (pintype "passive+no_connect"))
    )
    (net (code "29") (name "unconnected-(IC6N-NC-PadAE6)") (class "Default")
      (node (ref "IC6") (pin "AE6") (pinfunction "NC_AE6") (pintype "passive+no_connect"))
    )
    (net (code "30") (name "unconnected-(IC6N-NC-PadAF3)") (class "Default")
      (node (ref "IC6") (pin "AF3") (pinfunction "NC_AF3") (pintype "passive+no_connect"))
    )
    (net (code "31") (name "unconnected-(IC6N-NC-PadAF4)") (class "Default")
      (node (ref "IC6") (pin "AF4") (pinfunction "NC_AF4") (pintype "passive+no_connect"))
    )
    (net (code "32") (name "unconnected-(IC6N-NC-PadAF7)") (class "Default")
      (node (ref "IC6") (pin "AF7") (pinfunction "NC_AF7") (pintype "passive+no_connect"))
    )
    (net (code "33") (name "unconnected-(IC6N-NC-PadAF8)") (class "Default")
      (node (ref "IC6") (pin "AF8") (pinfunction "NC_AF8") (pintype "passive+no_connect"))
    )
    (net (code "34") (name "unconnected-(IC6N-NC-PadW5)") (class "Default")
      (node (ref "IC6") (pin "W5") (pinfunction "NC_W5") (pintype "passive+no_connect"))
    )
    (net (code "35") (name "unconnected-(IC6N-NC-PadW6)") (class "Default")
      (node (ref "IC6") (pin "W6") (pinfunction "NC_W6") (pintype "passive+no_connect"))
    )
  )
)
